# MR_UartConnector.net
KiCad netlist of a schematic drawn in Altium Designer
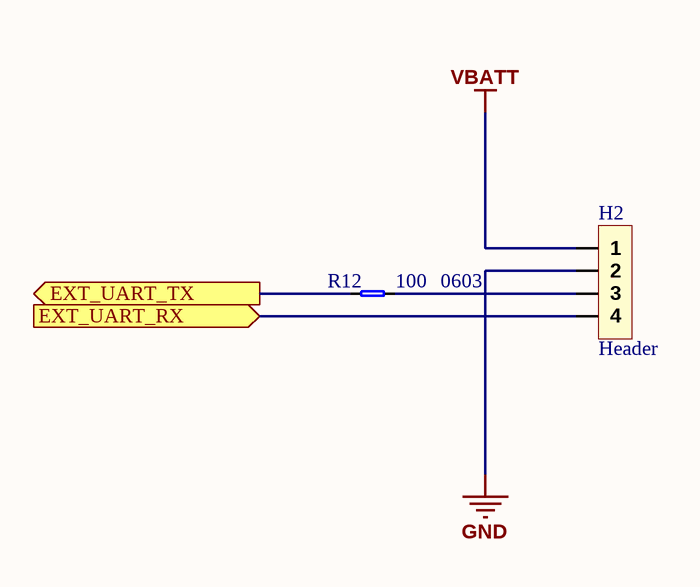
[diagram p0: MR_UartConnector.SchDoc]

(export (version "E")
  (design (tool "Eeschema 10.0.6"))
  (components
    (comp (ref "H2")
      (value "Header")
      (footprint "HE14 1x4 Straight")
      (description "Header 4x1 PIns")
      (libsource (lib "MiniRobot") (part "Header_4x1"))
    )
    (comp (ref "R12")
      (value "100")
      (footprint "0603_RES_LD")
      (description "Resistor")
      (fields (field (name "PACKAGE") "0603"))
      (libsource (lib "MiniRobot") (part "Resistor"))
    )
  )
  (nets
    (net (code "1") (name "/EXT_UART_RX") (class "Default")
      (node (ref "H2") (pin "4") (pinfunction "4_4") (pintype "passive"))
    )
    (net (code "2") (name "/EXT_UART_TX") (class "Default")
      (node (ref "R12") (pin "1") (pinfunction "1_1") (pintype "passive"))
    )
    (net (code "3") (name "GND") (class "Default")
      (node (ref "H2") (pin "2") (pinfunction "2_2") (pintype "passive"))
    )
    (net (code "4") (name "Net-(H2-Pad3)") (class "Default")
      (node (ref "H2") (pin "3") (pinfunction "3_3") (pintype "passive"))
      (node (ref "R12") (pin "2") (pinfunction "2_2") (pintype "passive"))
    )
    (net (code "5") (name "VBATT") (class "Default")
      (node (ref "H2") (pin "1") (pinfunction "1_1") (pintype "passive"))
    )
  )
)
